# connection.net
KiCad netlist of a schematic drawn in EAGLE
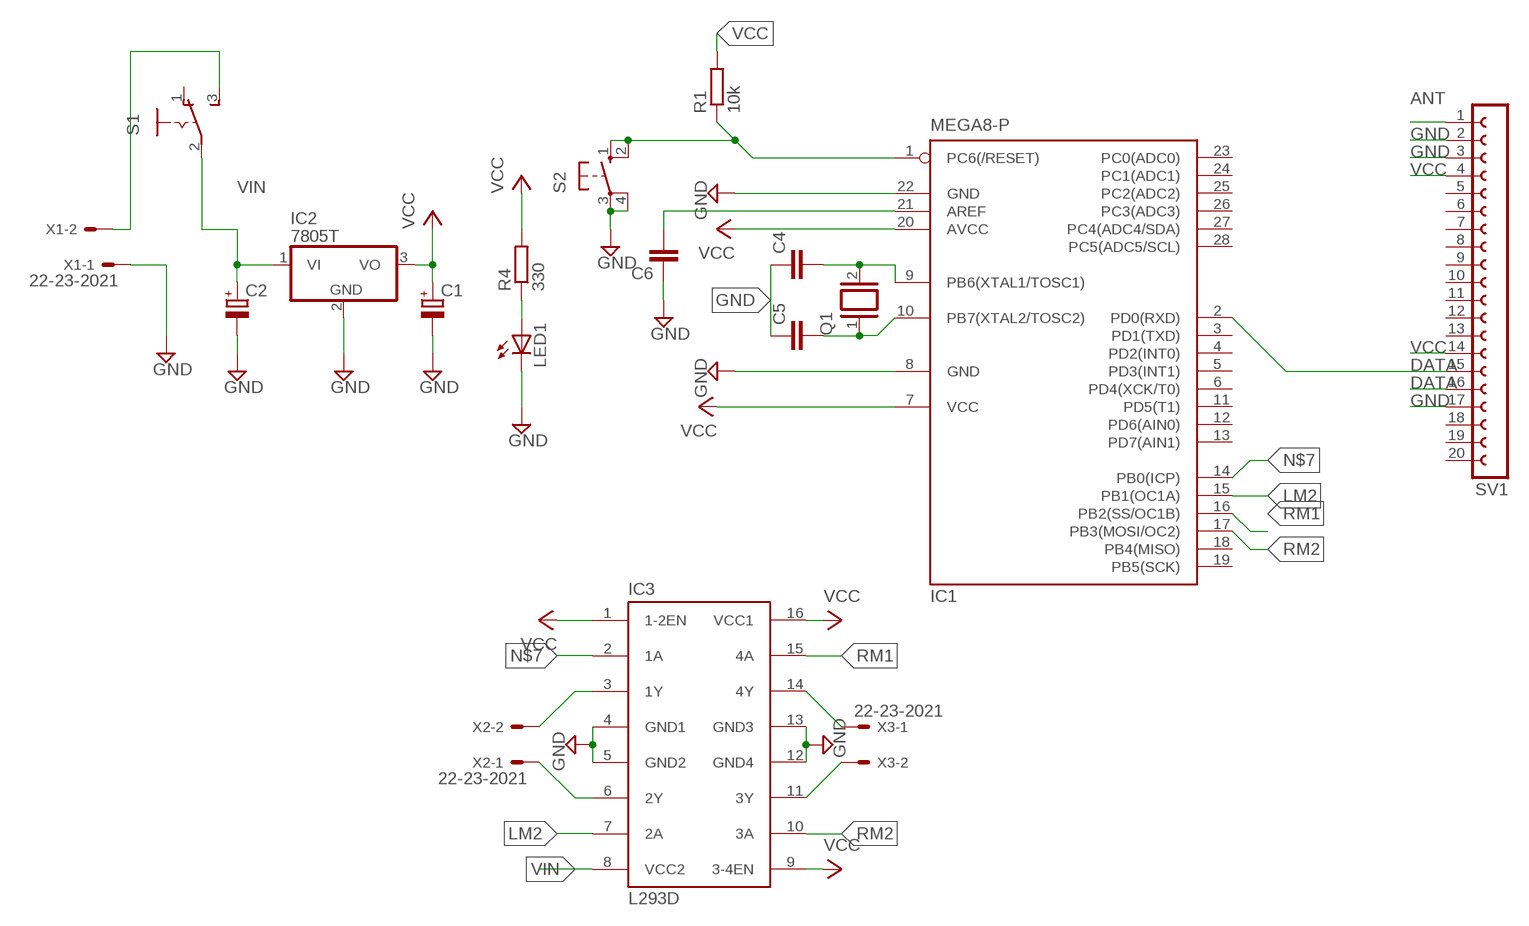
[diagram p0: schematic, sheet 1]

(export (version "E")
  (design (tool "Eeschema 10.0.6"))
  (components
    (comp (ref "C1")
      (value "CPOL-EUE3.5-8")
      (footprint "eagle-import:E3,5-8")
      (libsource (lib "eagle-import") (part "CPOL-EUE3.5-8"))
    )
    (comp (ref "C2")
      (value "CPOL-EUE3.5-8")
      (footprint "eagle-import:E3,5-8")
      (libsource (lib "eagle-import") (part "CPOL-EUE3.5-8"))
    )
    (comp (ref "C4")
      (value "C5/2.5")
      (footprint "eagle-import:C5B2.5")
      (libsource (lib "eagle-import") (part "C5/2.5"))
    )
    (comp (ref "C5")
      (value "C5/2.5")
      (footprint "eagle-import:C5B2.5")
      (libsource (lib "eagle-import") (part "C5/2.5"))
    )
    (comp (ref "C6")
      (value "C5/2.5")
      (footprint "eagle-import:C5B2.5")
      (libsource (lib "eagle-import") (part "C5/2.5"))
    )
    (comp (ref "IC1")
      (value "MEGA8-P")
      (footprint "eagle-import:DIL28-3")
      (libsource (lib "eagle-import") (part "MEGA8-P"))
    )
    (comp (ref "IC2")
      (value "7805T")
      (footprint "eagle-import:TO220H")
      (libsource (lib "eagle-import") (part "78T05"))
    )
    (comp (ref "IC3")
      (value "L293D")
      (footprint "eagle-import:DIL16")
      (libsource (lib "eagle-import") (part "L293D"))
    )
    (comp (ref "LED1")
      (value "LED5MM")
      (footprint "eagle-import:LED5MM")
      (libsource (lib "eagle-import") (part "LED5MM"))
    )
    (comp (ref "Q1")
      (value "XTAL/S")
      (footprint "eagle-import:QS")
      (libsource (lib "eagle-import") (part "XTAL/S"))
    )
    (comp (ref "R1")
      (value "10k")
      (footprint "eagle-import:0207_10")
      (libsource (lib "eagle-import") (part "R-EU_0207/10"))
    )
    (comp (ref "R4")
      (value "330")
      (footprint "eagle-import:0207_10")
      (libsource (lib "eagle-import") (part "R-EU_0207/10"))
    )
    (comp (ref "S1")
      (value "255SB")
      (footprint "eagle-import:255SB")
      (libsource (lib "eagle-import") (part "255SB"))
    )
    (comp (ref "S2")
      (value "10-XX")
      (footprint "eagle-import:B3F-10XX")
      (fields (field (name "MPN") "B3F-1000"))
      (libsource (lib "eagle-import") (part "10-XX"))
    )
    (comp (ref "SV1")
      (value "FE20-1")
      (footprint "eagle-import:FE20")
      (libsource (lib "eagle-import") (part "FE20-1"))
    )
    (comp (ref "X1")
      (value "22-23-2021")
      (footprint "eagle-import:22-23-2021")
      (fields (field (name "MF") "MOLEX"))
      (libsource (lib "eagle-import") (part "22-23-2021"))
    )
    (comp (ref "X2")
      (value "22-23-2021")
      (footprint "eagle-import:22-23-2021")
      (fields (field (name "MF") "MOLEX"))
      (libsource (lib "eagle-import") (part "22-23-2021"))
    )
    (comp (ref "X3")
      (value "22-23-2021")
      (footprint "eagle-import:22-23-2021")
      (fields (field (name "MF") "MOLEX"))
      (libsource (lib "eagle-import") (part "22-23-2021"))
    )
  )
  (nets
    (net (code "1") (name "/ANT") (class "Default")
      (node (ref "SV1") (pin "1") (pinfunction "1_1") (pintype "passive"))
    )
    (net (code "2") (name "/DATA") (class "Default")
      (node (ref "IC1") (pin "2") (pinfunction "PD0(RXD)_2") (pintype "bidirectional"))
      (node (ref "SV1") (pin "15") (pinfunction "15_15") (pintype "passive"))
      (node (ref "SV1") (pin "16") (pinfunction "16_16") (pintype "passive"))
    )
    (net (code "3") (name "GND") (class "Default")
      (node (ref "C1") (pin "-") (pinfunction "-_-") (pintype "passive"))
      (node (ref "C2") (pin "-") (pinfunction "-_-") (pintype "passive"))
      (node (ref "C4") (pin "1") (pinfunction "1_1") (pintype "passive"))
      (node (ref "C5") (pin "1") (pinfunction "1_1") (pintype "passive"))
      (node (ref "C6") (pin "1") (pinfunction "1_1") (pintype "passive"))
      (node (ref "IC1") (pin "22") (pinfunction "GND_22") (pintype "power_in"))
      (node (ref "IC1") (pin "8") (pinfunction "GND_8") (pintype "power_in"))
      (node (ref "IC2") (pin "2") (pinfunction "GND_2") (pintype "passive"))
      (node (ref "IC3") (pin "12") (pinfunction "GND4_12") (pintype "power_in"))
      (node (ref "IC3") (pin "13") (pinfunction "GND3_13") (pintype "power_in"))
      (node (ref "IC3") (pin "4") (pinfunction "GND1_4") (pintype "power_in"))
      (node (ref "IC3") (pin "5") (pinfunction "GND2_5") (pintype "power_in"))
      (node (ref "LED1") (pin "K") (pinfunction "C_K") (pintype "passive"))
      (node (ref "S2") (pin "3") (pinfunction "P_3") (pintype "passive"))
      (node (ref "S2") (pin "4") (pinfunction "P1_4") (pintype "passive"))
      (node (ref "SV1") (pin "17") (pinfunction "17_17") (pintype "passive"))
      (node (ref "SV1") (pin "2") (pinfunction "2_2") (pintype "passive"))
      (node (ref "SV1") (pin "3") (pinfunction "3_3") (pintype "passive"))
      (node (ref "X1") (pin "1") (pinfunction "S_1") (pintype "passive"))
    )
    (net (code "4") (name "LM2") (class "Default")
      (node (ref "IC1") (pin "15") (pinfunction "PB1(OC1A)_15") (pintype "bidirectional"))
      (node (ref "IC3") (pin "7") (pinfunction "2A_7") (pintype "input"))
    )
    (net (code "5") (name "N$7") (class "Default")
      (node (ref "IC1") (pin "14") (pinfunction "PB0(ICP)_14") (pintype "bidirectional"))
      (node (ref "IC3") (pin "2") (pinfunction "1A_2") (pintype "input"))
    )
    (net (code "6") (name "Net-(IC1-AREF)") (class "Default")
      (node (ref "C6") (pin "2") (pinfunction "2_2") (pintype "passive"))
      (node (ref "IC1") (pin "21") (pinfunction "AREF_21") (pintype "passive"))
    )
    (net (code "7") (name "Net-(IC1-PB6(XTAL1{slash}TOSC1))") (class "Default")
      (node (ref "C4") (pin "2") (pinfunction "2_2") (pintype "passive"))
      (node (ref "IC1") (pin "9") (pinfunction "PB6(XTAL1/TOSC1)_9") (pintype "bidirectional"))
      (node (ref "Q1") (pin "2") (pinfunction "2_2") (pintype "passive"))
    )
    (net (code "8") (name "Net-(IC1-PB7(XTAL2{slash}TOSC2))") (class "Default")
      (node (ref "C5") (pin "2") (pinfunction "2_2") (pintype "passive"))
      (node (ref "IC1") (pin "10") (pinfunction "PB7(XTAL2/TOSC2)_10") (pintype "bidirectional"))
      (node (ref "Q1") (pin "1") (pinfunction "1_1") (pintype "passive"))
    )
    (net (code "9") (name "Net-(IC1-PC6({slash}RESET))") (class "Default")
      (node (ref "IC1") (pin "1") (pinfunction "PC6(/RESET)_1") (pintype "bidirectional"))
      (node (ref "R1") (pin "1") (pinfunction "1_1") (pintype "passive"))
      (node (ref "S2") (pin "1") (pinfunction "S_1") (pintype "passive"))
      (node (ref "S2") (pin "2") (pinfunction "S1_2") (pintype "passive"))
    )
    (net (code "10") (name "Net-(IC3-1Y)") (class "Default")
      (node (ref "IC3") (pin "3") (pinfunction "1Y_3") (pintype "output"))
      (node (ref "X2") (pin "2") (pinfunction "S_2") (pintype "passive"))
    )
    (net (code "11") (name "Net-(IC3-2Y)") (class "Default")
      (node (ref "IC3") (pin "6") (pinfunction "2Y_6") (pintype "output"))
      (node (ref "X2") (pin "1") (pinfunction "S_1") (pintype "passive"))
    )
    (net (code "12") (name "Net-(IC3-3Y)") (class "Default")
      (node (ref "IC3") (pin "11") (pinfunction "3Y_11") (pintype "output"))
      (node (ref "X3") (pin "2") (pinfunction "S_2") (pintype "passive"))
    )
    (net (code "13") (name "Net-(IC3-4Y)") (class "Default")
      (node (ref "IC3") (pin "14") (pinfunction "4Y_14") (pintype "output"))
      (node (ref "X3") (pin "1") (pinfunction "S_1") (pintype "passive"))
    )
    (net (code "14") (name "Net-(LED1-PadA)") (class "Default")
      (node (ref "LED1") (pin "A") (pinfunction "A_A") (pintype "passive"))
      (node (ref "R4") (pin "1") (pinfunction "1_1") (pintype "passive"))
    )
    (net (code "15") (name "Net-(S1-S)") (class "Default")
      (node (ref "S1") (pin "3") (pinfunction "S_3") (pintype "passive"))
      (node (ref "X1") (pin "2") (pinfunction "S_2") (pintype "passive"))
    )
    (net (code "16") (name "RM1") (class "Default")
      (node (ref "IC1") (pin "16") (pinfunction "PB2(SS/OC1B)_16") (pintype "bidirectional"))
      (node (ref "IC3") (pin "15") (pinfunction "4A_15") (pintype "input"))
    )
    (net (code "17") (name "RM2") (class "Default")
      (node (ref "IC1") (pin "17") (pinfunction "PB3(MOSI/OC2)_17") (pintype "bidirectional"))
      (node (ref "IC3") (pin "10") (pinfunction "3A_10") (pintype "input"))
    )
    (net (code "18") (name "VCC") (class "Default")
      (node (ref "C1") (pin "+") (pinfunction "+_+") (pintype "passive"))
      (node (ref "IC1") (pin "20") (pinfunction "AVCC_20") (pintype "power_in"))
      (node (ref "IC1") (pin "7") (pinfunction "VCC_7") (pintype "power_in"))
      (node (ref "IC2") (pin "3") (pinfunction "VO_3") (pintype "passive"))
      (node (ref "IC3") (pin "1") (pinfunction "1-2EN_1") (pintype "input"))
      (node (ref "IC3") (pin "16") (pinfunction "VCC1_16") (pintype "power_in"))
      (node (ref "IC3") (pin "9") (pinfunction "3-4EN_9") (pintype "input"))
      (node (ref "R1") (pin "2") (pinfunction "2_2") (pintype "passive"))
      (node (ref "R4") (pin "2") (pinfunction "2_2") (pintype "passive"))
      (node (ref "SV1") (pin "14") (pinfunction "14_14") (pintype "passive"))
      (node (ref "SV1") (pin "4") (pinfunction "4_4") (pintype "passive"))
    )
    (net (code "19") (name "VIN") (class "Default")
      (node (ref "C2") (pin "+") (pinfunction "+_+") (pintype "passive"))
      (node (ref "IC2") (pin "1") (pinfunction "VI_1") (pintype "input"))
      (node (ref "IC3") (pin "8") (pinfunction "VCC2_8") (pintype "power_in"))
      (node (ref "S1") (pin "2") (pinfunction "P_2") (pintype "passive"))
    )
    (net (code "20") (name "unconnected-(IC1-PB4(MISO)-Pad18)") (class "Default")
      (node (ref "IC1") (pin "18") (pinfunction "PB4(MISO)_18") (pintype "bidirectional"))
    )
    (net (code "21") (name "unconnected-(IC1-PB5(SCK)-Pad19)") (class "Default")
      (node (ref "IC1") (pin "19") (pinfunction "PB5(SCK)_19") (pintype "bidirectional"))
    )
    (net (code "22") (name "unconnected-(IC1-PC0(ADC0)-Pad23)") (class "Default")
      (node (ref "IC1") (pin "23") (pinfunction "PC0(ADC0)_23") (pintype "bidirectional"))
    )
    (net (code "23") (name "unconnected-(IC1-PC1(ADC1)-Pad24)") (class "Default")
      (node (ref "IC1") (pin "24") (pinfunction "PC1(ADC1)_24") (pintype "bidirectional"))
    )
    (net (code "24") (name "unconnected-(IC1-PC2(ADC2)-Pad25)") (class "Default")
      (node (ref "IC1") (pin "25") (pinfunction "PC2(ADC2)_25") (pintype "bidirectional"))
    )
    (net (code "25") (name "unconnected-(IC1-PC3(ADC3)-Pad26)") (class "Default")
      (node (ref "IC1") (pin "26") (pinfunction "PC3(ADC3)_26") (pintype "bidirectional"))
    )
    (net (code "26") (name "unconnected-(IC1-PC4(ADC4{slash}SDA)-Pad27)") (class "Default")
      (node (ref "IC1") (pin "27") (pinfunction "PC4(ADC4/SDA)_27") (pintype "bidirectional"))
    )
    (net (code "27") (name "unconnected-(IC1-PC5(ADC5{slash}SCL)-Pad28)") (class "Default")
      (node (ref "IC1") (pin "28") (pinfunction "PC5(ADC5/SCL)_28") (pintype "bidirectional"))
    )
    (net (code "28") (name "unconnected-(IC1-PD1(TXD)-Pad3)") (class "Default")
      (node (ref "IC1") (pin "3") (pinfunction "PD1(TXD)_3") (pintype "bidirectional"))
    )
    (net (code "29") (name "unconnected-(IC1-PD2(INT0)-Pad4)") (class "Default")
      (node (ref "IC1") (pin "4") (pinfunction "PD2(INT0)_4") (pintype "bidirectional"))
    )
    (net (code "30") (name "unconnected-(IC1-PD3(INT1)-Pad5)") (class "Default")
      (node (ref "IC1") (pin "5") (pinfunction "PD3(INT1)_5") (pintype "bidirectional"))
    )
    (net (code "31") (name "unconnected-(IC1-PD4(XCK{slash}T0)-Pad6)") (class "Default")
      (node (ref "IC1") (pin "6") (pinfunction "PD4(XCK/T0)_6") (pintype "bidirectional"))
    )
    (net (code "32") (name "unconnected-(IC1-PD5(T1)-Pad11)") (class "Default")
      (node (ref "IC1") (pin "11") (pinfunction "PD5(T1)_11") (pintype "bidirectional"))
    )
    (net (code "33") (name "unconnected-(IC1-PD6(AIN0)-Pad12)") (class "Default")
      (node (ref "IC1") (pin "12") (pinfunction "PD6(AIN0)_12") (pintype "bidirectional"))
    )
    (net (code "34") (name "unconnected-(IC1-PD7(AIN1)-Pad13)") (class "Default")
      (node (ref "IC1") (pin "13") (pinfunction "PD7(AIN1)_13") (pintype "bidirectional"))
    )
    (net (code "35") (name "unconnected-(S1-O-Pad1)") (class "Default")
      (node (ref "S1") (pin "1") (pinfunction "O_1") (pintype "passive"))
    )
    (net (code "36") (name "unconnected-(SV1-Pad5)") (class "Default")
      (node (ref "SV1") (pin "5") (pinfunction "5_5") (pintype "passive"))
    )
    (net (code "37") (name "unconnected-(SV1-Pad6)") (class "Default")
      (node (ref "SV1") (pin "6") (pinfunction "6_6") (pintype "passive"))
    )
    (net (code "38") (name "unconnected-(SV1-Pad7)") (class "Default")
      (node (ref "SV1") (pin "7") (pinfunction "7_7") (pintype "passive"))
    )
    (net (code "39") (name "unconnected-(SV1-Pad8)") (class "Default")
      (node (ref "SV1") (pin "8") (pinfunction "8_8") (pintype "passive"))
    )
    (net (code "40") (name "unconnected-(SV1-Pad9)") (class "Default")
      (node (ref "SV1") (pin "9") (pinfunction "9_9") (pintype "passive"))
    )
    (net (code "41") (name "unconnected-(SV1-Pad10)") (class "Default")
      (node (ref "SV1") (pin "10") (pinfunction "10_10") (pintype "passive"))
    )
    (net (code "42") (name "unconnected-(SV1-Pad11)") (class "Default")
      (node (ref "SV1") (pin "11") (pinfunction "11_11") (pintype "passive"))
    )
    (net (code "43") (name "unconnected-(SV1-Pad12)") (class "Default")
      (node (ref "SV1") (pin "12") (pinfunction "12_12") (pintype "passive"))
    )
    (net (code "44") (name "unconnected-(SV1-Pad13)") (class "Default")
      (node (ref "SV1") (pin "13") (pinfunction "13_13") (pintype "passive"))
    )
    (net (code "45") (name "unconnected-(SV1-Pad18)") (class "Default")
      (node (ref "SV1") (pin "18") (pinfunction "18_18") (pintype "passive"))
    )
    (net (code "46") (name "unconnected-(SV1-Pad19)") (class "Default")
      (node (ref "SV1") (pin "19") (pinfunction "19_19") (pintype "passive"))
    )
    (net (code "47") (name "unconnected-(SV1-Pad20)") (class "Default")
      (node (ref "SV1") (pin "20") (pinfunction "20_20") (pintype "passive"))
    )
  )
)
